# Connectors.net
KiCad netlist of a schematic drawn in Altium Designer
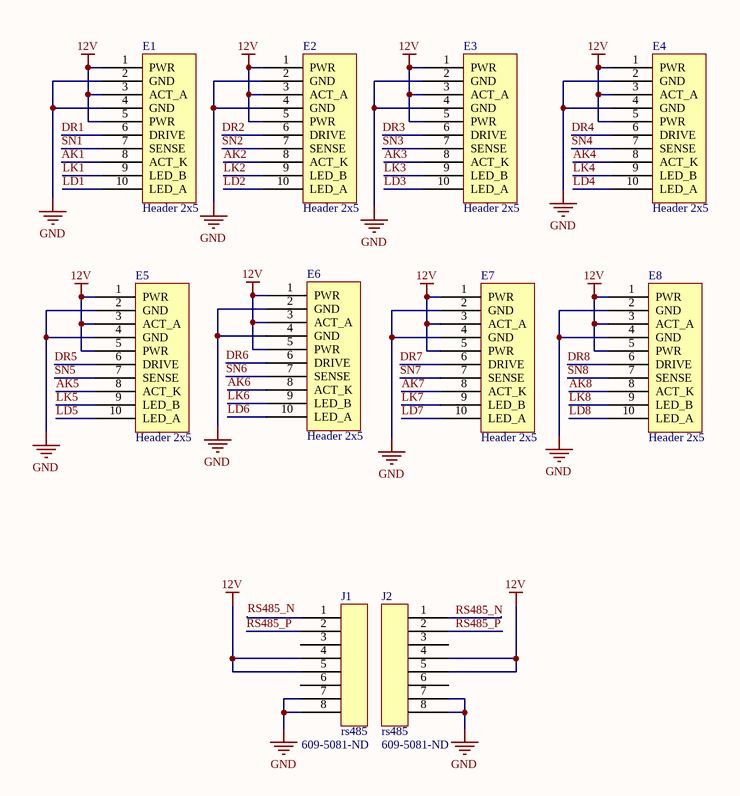
[diagram p0: Connectors.SchDoc]

(export (version "E")
  (design (tool "Eeschema 10.0.6"))
  (components
    (comp (ref "E1")
      (value "Header 2x5")
      (footprint "2x5")
      (description "Header")
      (libsource (lib "DoorNode") (part "Header 2x5a"))
    )
    (comp (ref "E2")
      (value "Header 2x5")
      (footprint "2x5")
      (description "Header")
      (libsource (lib "DoorNode") (part "Header 2x5a"))
    )
    (comp (ref "E3")
      (value "Header 2x5")
      (footprint "2x5")
      (description "Header")
      (libsource (lib "DoorNode") (part "Header 2x5a"))
    )
    (comp (ref "E4")
      (value "Header 2x5")
      (footprint "2x5")
      (description "Header")
      (libsource (lib "DoorNode") (part "Header 2x5a"))
    )
    (comp (ref "E5")
      (value "Header 2x5")
      (footprint "2x5")
      (description "Header")
      (libsource (lib "DoorNode") (part "Header 2x5a"))
    )
    (comp (ref "E6")
      (value "Header 2x5")
      (footprint "2x5")
      (description "Header")
      (libsource (lib "DoorNode") (part "Header 2x5a"))
    )
    (comp (ref "E7")
      (value "Header 2x5")
      (footprint "2x5")
      (description "Header")
      (libsource (lib "DoorNode") (part "Header 2x5a"))
    )
    (comp (ref "E8")
      (value "Header 2x5")
      (footprint "2x5")
      (description "Header")
      (libsource (lib "DoorNode") (part "Header 2x5a"))
    )
    (comp (ref "J1")
      (value "rs485")
      (footprint "RJ45")
      (description "rj45")
      (fields (field (name "SUPPLIER PART NUMBER 1") "609-5081-ND"))
      (libsource (lib "") (part "rj45_1"))
    )
    (comp (ref "J2")
      (value "rs485")
      (footprint "RJ45")
      (description "rj45")
      (fields (field (name "SUPPLIER PART NUMBER 1") "609-5081-ND"))
      (libsource (lib "ToolDoorController") (part "rj45"))
    )
  )
  (nets
    (net (code "1") (name "/AK1") (class "Default")
      (node (ref "E1") (pin "8") (pinfunction "ACT_K_8") (pintype "power_in"))
    )
    (net (code "2") (name "/AK2") (class "Default")
      (node (ref "E2") (pin "8") (pinfunction "ACT_K_8") (pintype "power_in"))
    )
    (net (code "3") (name "/AK3") (class "Default")
      (node (ref "E3") (pin "8") (pinfunction "ACT_K_8") (pintype "power_in"))
    )
    (net (code "4") (name "/AK4") (class "Default")
      (node (ref "E4") (pin "8") (pinfunction "ACT_K_8") (pintype "power_in"))
    )
    (net (code "5") (name "/AK5") (class "Default")
      (node (ref "E5") (pin "8") (pinfunction "ACT_K_8") (pintype "power_in"))
    )
    (net (code "6") (name "/AK6") (class "Default")
      (node (ref "E6") (pin "8") (pinfunction "ACT_K_8") (pintype "power_in"))
    )
    (net (code "7") (name "/AK7") (class "Default")
      (node (ref "E7") (pin "8") (pinfunction "ACT_K_8") (pintype "power_in"))
    )
    (net (code "8") (name "/AK8") (class "Default")
      (node (ref "E8") (pin "8") (pinfunction "ACT_K_8") (pintype "power_in"))
    )
    (net (code "9") (name "/DR1") (class "Default")
      (node (ref "E1") (pin "6") (pinfunction "DRIVE_6") (pintype "power_in"))
    )
    (net (code "10") (name "/DR2") (class "Default")
      (node (ref "E2") (pin "6") (pinfunction "DRIVE_6") (pintype "power_in"))
    )
    (net (code "11") (name "/DR3") (class "Default")
      (node (ref "E3") (pin "6") (pinfunction "DRIVE_6") (pintype "power_in"))
    )
    (net (code "12") (name "/DR4") (class "Default")
      (node (ref "E4") (pin "6") (pinfunction "DRIVE_6") (pintype "power_in"))
    )
    (net (code "13") (name "/DR5") (class "Default")
      (node (ref "E5") (pin "6") (pinfunction "DRIVE_6") (pintype "power_in"))
    )
    (net (code "14") (name "/DR6") (class "Default")
      (node (ref "E6") (pin "6") (pinfunction "DRIVE_6") (pintype "power_in"))
    )
    (net (code "15") (name "/DR7") (class "Default")
      (node (ref "E7") (pin "6") (pinfunction "DRIVE_6") (pintype "power_in"))
    )
    (net (code "16") (name "/DR8") (class "Default")
      (node (ref "E8") (pin "6") (pinfunction "DRIVE_6") (pintype "power_in"))
    )
    (net (code "17") (name "/LD1") (class "Default")
      (node (ref "E1") (pin "10") (pinfunction "LED_A_10") (pintype "power_in"))
    )
    (net (code "18") (name "/LD2") (class "Default")
      (node (ref "E2") (pin "10") (pinfunction "LED_A_10") (pintype "power_in"))
    )
    (net (code "19") (name "/LD3") (class "Default")
      (node (ref "E3") (pin "10") (pinfunction "LED_A_10") (pintype "power_in"))
    )
    (net (code "20") (name "/LD4") (class "Default")
      (node (ref "E4") (pin "10") (pinfunction "LED_A_10") (pintype "power_in"))
    )
    (net (code "21") (name "/LD5") (class "Default")
      (node (ref "E5") (pin "10") (pinfunction "LED_A_10") (pintype "power_in"))
    )
    (net (code "22") (name "/LD6") (class "Default")
      (node (ref "E6") (pin "10") (pinfunction "LED_A_10") (pintype "power_in"))
    )
    (net (code "23") (name "/LD7") (class "Default")
      (node (ref "E7") (pin "10") (pinfunction "LED_A_10") (pintype "power_in"))
    )
    (net (code "24") (name "/LD8") (class "Default")
      (node (ref "E8") (pin "10") (pinfunction "LED_A_10") (pintype "power_in"))
    )
    (net (code "25") (name "/LK1") (class "Default")
      (node (ref "E1") (pin "9") (pinfunction "LED_B_9") (pintype "power_in"))
    )
    (net (code "26") (name "/LK2") (class "Default")
      (node (ref "E2") (pin "9") (pinfunction "LED_B_9") (pintype "power_in"))
    )
    (net (code "27") (name "/LK3") (class "Default")
      (node (ref "E3") (pin "9") (pinfunction "LED_B_9") (pintype "power_in"))
    )
    (net (code "28") (name "/LK4") (class "Default")
      (node (ref "E4") (pin "9") (pinfunction "LED_B_9") (pintype "power_in"))
    )
    (net (code "29") (name "/LK5") (class "Default")
      (node (ref "E5") (pin "9") (pinfunction "LED_B_9") (pintype "power_in"))
    )
    (net (code "30") (name "/LK6") (class "Default")
      (node (ref "E6") (pin "9") (pinfunction "LED_B_9") (pintype "power_in"))
    )
    (net (code "31") (name "/LK7") (class "Default")
      (node (ref "E7") (pin "9") (pinfunction "LED_B_9") (pintype "power_in"))
    )
    (net (code "32") (name "/LK8") (class "Default")
      (node (ref "E8") (pin "9") (pinfunction "LED_B_9") (pintype "power_in"))
    )
    (net (code "33") (name "/RS485_N") (class "Default")
      (node (ref "J1") (pin "1") (pinfunction "1_1") (pintype "power_in"))
      (node (ref "J2") (pin "1") (pinfunction "1_1") (pintype "power_in"))
    )
    (net (code "34") (name "/RS485_P") (class "Default")
      (node (ref "J1") (pin "2") (pinfunction "2_2") (pintype "power_in"))
      (node (ref "J2") (pin "2") (pinfunction "2_2") (pintype "power_in"))
    )
    (net (code "35") (name "/SN1") (class "Default")
      (node (ref "E1") (pin "7") (pinfunction "SENSE_7") (pintype "power_in"))
    )
    (net (code "36") (name "/SN2") (class "Default")
      (node (ref "E2") (pin "7") (pinfunction "SENSE_7") (pintype "power_in"))
    )
    (net (code "37") (name "/SN3") (class "Default")
      (node (ref "E3") (pin "7") (pinfunction "SENSE_7") (pintype "power_in"))
    )
    (net (code "38") (name "/SN4") (class "Default")
      (node (ref "E4") (pin "7") (pinfunction "SENSE_7") (pintype "power_in"))
    )
    (net (code "39") (name "/SN5") (class "Default")
      (node (ref "E5") (pin "7") (pinfunction "SENSE_7") (pintype "power_in"))
    )
    (net (code "40") (name "/SN6") (class "Default")
      (node (ref "E6") (pin "7") (pinfunction "SENSE_7") (pintype "power_in"))
    )
    (net (code "41") (name "/SN7") (class "Default")
      (node (ref "E7") (pin "7") (pinfunction "SENSE_7") (pintype "power_in"))
    )
    (net (code "42") (name "/SN8") (class "Default")
      (node (ref "E8") (pin "7") (pinfunction "SENSE_7") (pintype "power_in"))
    )
    (net (code "43") (name "12V") (class "Default")
      (node (ref "E1") (pin "1") (pinfunction "PWR_1") (pintype "power_in"))
      (node (ref "E1") (pin "3") (pinfunction "ACT_A_3") (pintype "power_in"))
      (node (ref "E1") (pin "5") (pinfunction "PWR_5") (pintype "power_in"))
      (node (ref "E2") (pin "1") (pinfunction "PWR_1") (pintype "power_in"))
      (node (ref "E2") (pin "3") (pinfunction "ACT_A_3") (pintype "power_in"))
      (node (ref "E2") (pin "5") (pinfunction "PWR_5") (pintype "power_in"))
      (node (ref "E3") (pin "1") (pinfunction "PWR_1") (pintype "power_in"))
      (node (ref "E3") (pin "3") (pinfunction "ACT_A_3") (pintype "power_in"))
      (node (ref "E3") (pin "5") (pinfunction "PWR_5") (pintype "power_in"))
      (node (ref "E4") (pin "1") (pinfunction "PWR_1") (pintype "power_in"))
      (node (ref "E4") (pin "3") (pinfunction "ACT_A_3") (pintype "power_in"))
      (node (ref "E4") (pin "5") (pinfunction "PWR_5") (pintype "power_in"))
      (node (ref "E5") (pin "1") (pinfunction "PWR_1") (pintype "power_in"))
      (node (ref "E5") (pin "3") (pinfunction "ACT_A_3") (pintype "power_in"))
      (node (ref "E5") (pin "5") (pinfunction "PWR_5") (pintype "power_in"))
      (node (ref "E6") (pin "1") (pinfunction "PWR_1") (pintype "power_in"))
      (node (ref "E6") (pin "3") (pinfunction "ACT_A_3") (pintype "power_in"))
      (node (ref "E6") (pin "5") (pinfunction "PWR_5") (pintype "power_in"))
      (node (ref "E7") (pin "1") (pinfunction "PWR_1") (pintype "power_in"))
      (node (ref "E7") (pin "3") (pinfunction "ACT_A_3") (pintype "power_in"))
      (node (ref "E7") (pin "5") (pinfunction "PWR_5") (pintype "power_in"))
      (node (ref "E8") (pin "1") (pinfunction "PWR_1") (pintype "power_in"))
      (node (ref "E8") (pin "3") (pinfunction "ACT_A_3") (pintype "power_in"))
      (node (ref "E8") (pin "5") (pinfunction "PWR_5") (pintype "power_in"))
      (node (ref "J1") (pin "4") (pinfunction "4_4") (pintype "power_in"))
      (node (ref "J1") (pin "5") (pinfunction "5_5") (pintype "power_in"))
      (node (ref "J2") (pin "4") (pinfunction "4_4") (pintype "power_in"))
      (node (ref "J2") (pin "5") (pinfunction "5_5") (pintype "power_in"))
    )
    (net (code "44") (name "GND") (class "Default")
      (node (ref "E1") (pin "2") (pinfunction "GND_2") (pintype "power_in"))
      (node (ref "E1") (pin "4") (pinfunction "GND_4") (pintype "power_in"))
      (node (ref "E2") (pin "2") (pinfunction "GND_2") (pintype "power_in"))
      (node (ref "E2") (pin "4") (pinfunction "GND_4") (pintype "power_in"))
      (node (ref "E3") (pin "2") (pinfunction "GND_2") (pintype "power_in"))
      (node (ref "E3") (pin "4") (pinfunction "GND_4") (pintype "power_in"))
      (node (ref "E4") (pin "2") (pinfunction "GND_2") (pintype "power_in"))
      (node (ref "E4") (pin "4") (pinfunction "GND_4") (pintype "power_in"))
      (node (ref "E5") (pin "2") (pinfunction "GND_2") (pintype "power_in"))
      (node (ref "E5") (pin "4") (pinfunction "GND_4") (pintype "power_in"))
      (node (ref "E6") (pin "2") (pinfunction "GND_2") (pintype "power_in"))
      (node (ref "E6") (pin "4") (pinfunction "GND_4") (pintype "power_in"))
      (node (ref "E7") (pin "2") (pinfunction "GND_2") (pintype "power_in"))
      (node (ref "E7") (pin "4") (pinfunction "GND_4") (pintype "power_in"))
      (node (ref "E8") (pin "2") (pinfunction "GND_2") (pintype "power_in"))
      (node (ref "E8") (pin "4") (pinfunction "GND_4") (pintype "power_in"))
      (node (ref "J1") (pin "7") (pinfunction "7_7") (pintype "power_in"))
      (node (ref "J1") (pin "8") (pinfunction "8_8") (pintype "power_in"))
      (node (ref "J2") (pin "7") (pinfunction "7_7") (pintype "power_in"))
      (node (ref "J2") (pin "8") (pinfunction "8_8") (pintype "power_in"))
    )
    (net (code "45") (name "unconnected-(J1-Pad3)") (class "Default")
      (node (ref "J1") (pin "3") (pinfunction "3_3") (pintype "power_in"))
    )
    (net (code "46") (name "unconnected-(J1-Pad6)") (class "Default")
      (node (ref "J1") (pin "6") (pinfunction "6_6") (pintype "power_in"))
    )
    (net (code "47") (name "unconnected-(J2-Pad3)") (class "Default")
      (node (ref "J2") (pin "3") (pinfunction "3_3") (pintype "power_in"))
    )
    (net (code "48") (name "unconnected-(J2-Pad6)") (class "Default")
      (node (ref "J2") (pin "6") (pinfunction "6_6") (pintype "power_in"))
    )
  )
)
